# MCU.net
KiCad netlist of a schematic drawn in Altium Designer
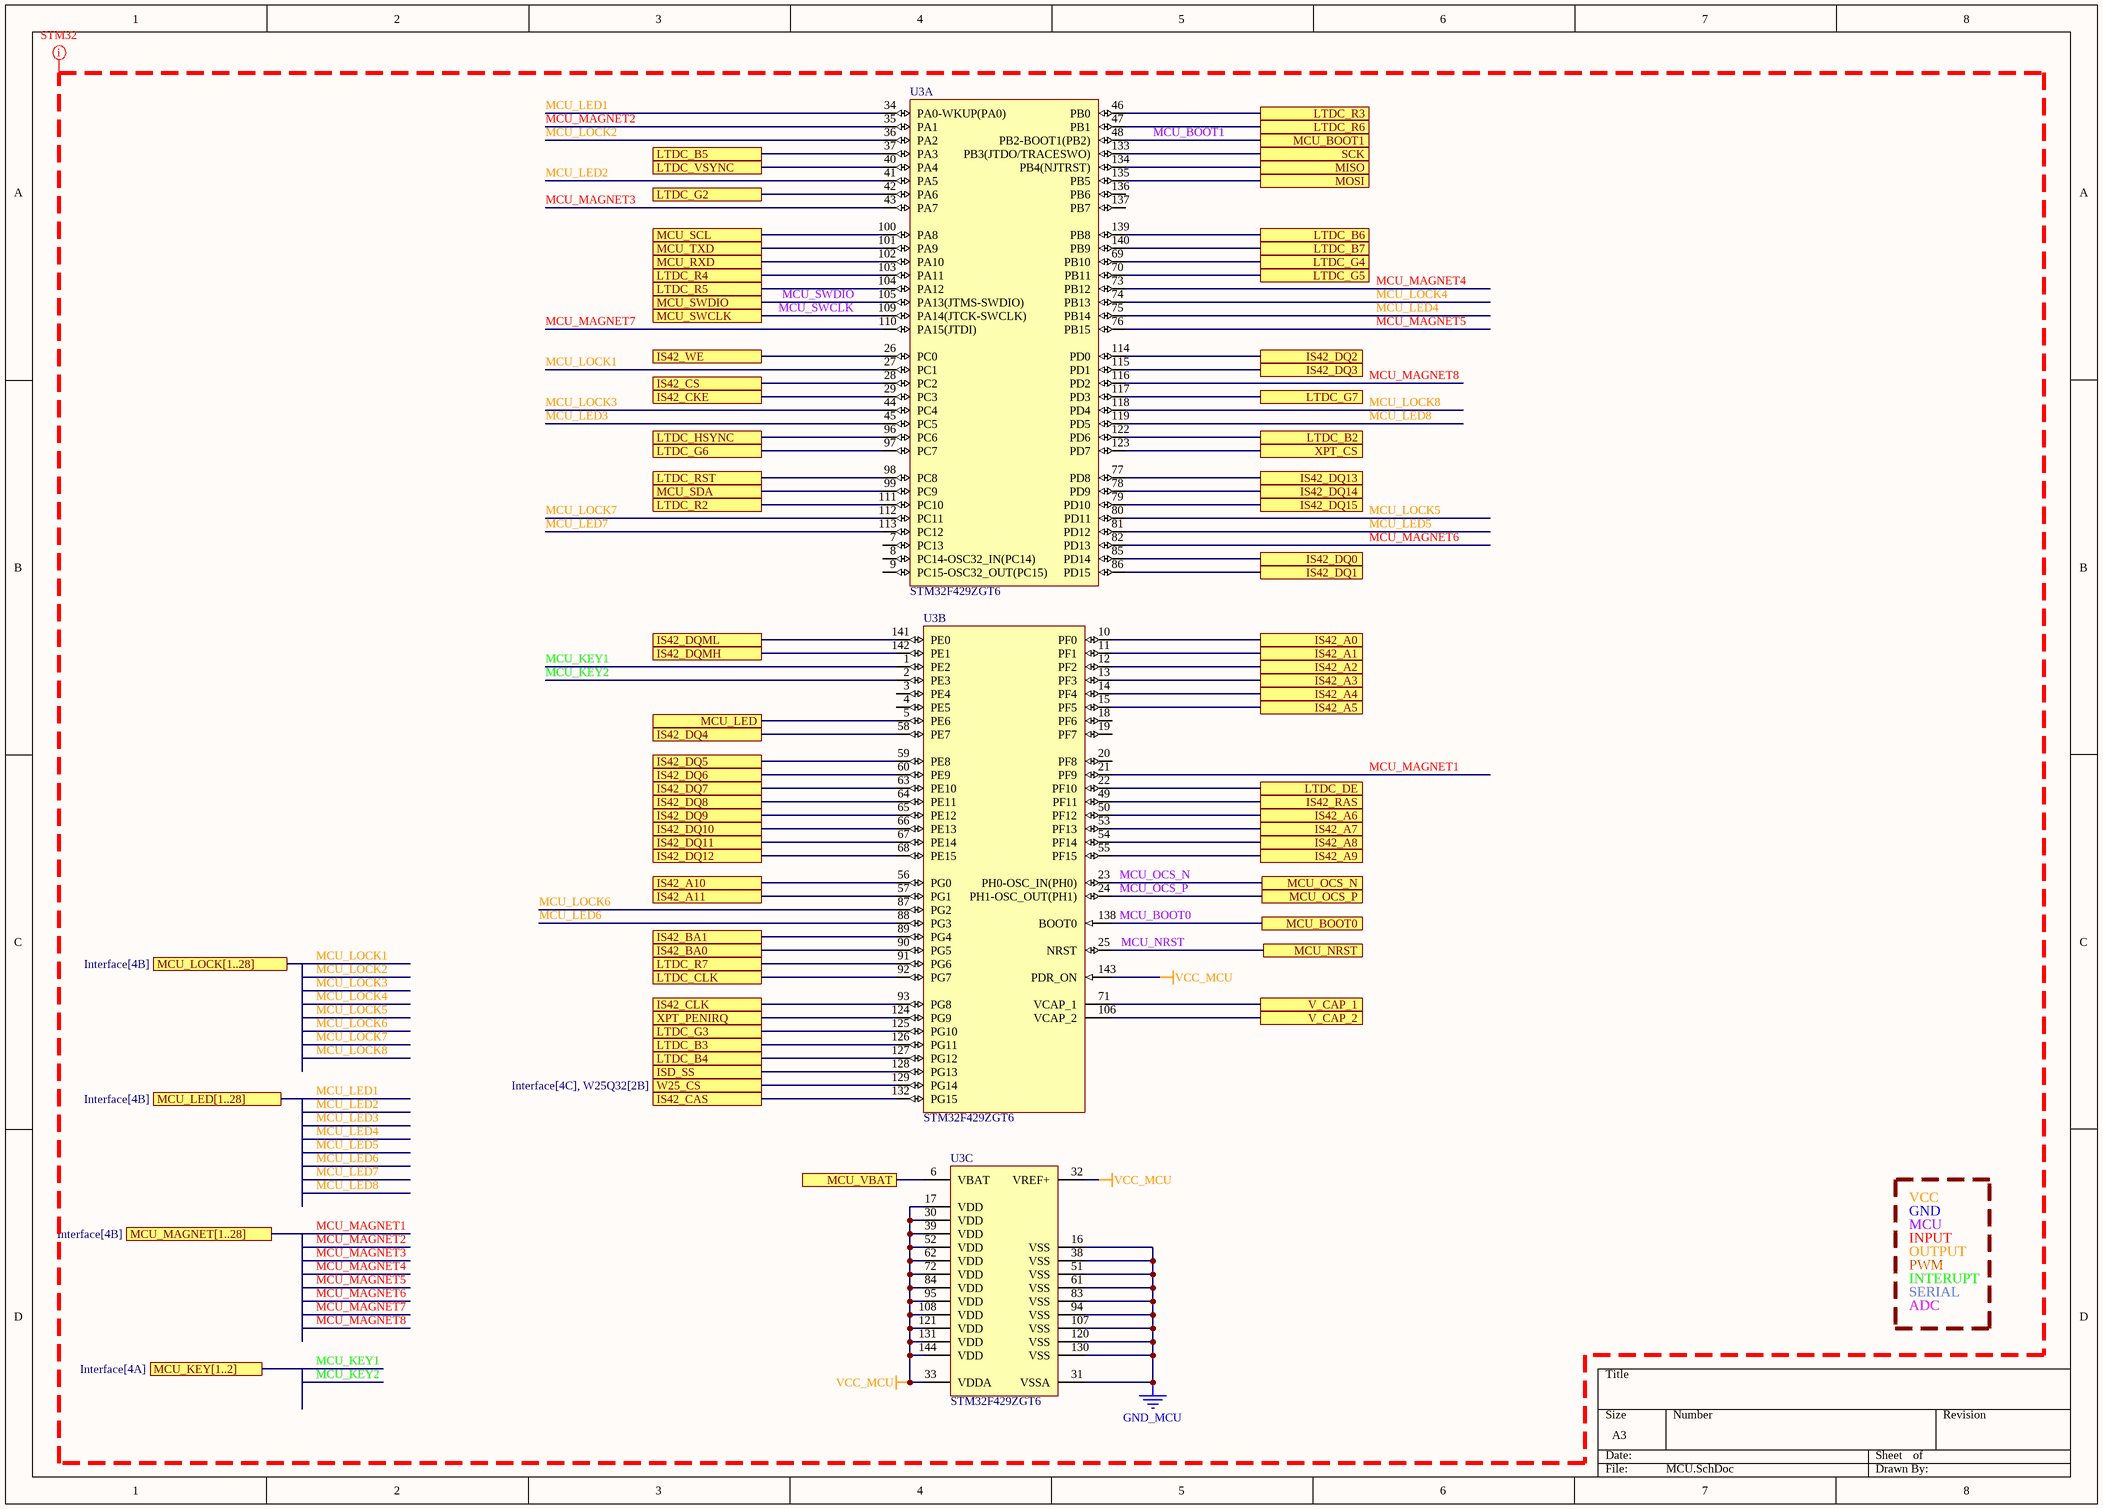
[diagram p0: MCU.SchDoc]

(export (version "E")
  (design (tool "Eeschema 10.0.6"))
  (components
    (comp (ref "U3")
      (value "STM32F429ZGT6")
      (footprint "STM-LQFP144_N")
      (fields (field (name "MANUFACTURER") "STMicroelectronics"))
      (libsource (lib "ST Microelectronics STM32 F4") (part "STM32F429ZGT6"))
    )
  )
  (nets
    (net (code "61") (name "/IS42_A0") (class "Default")
      (node (ref "U3") (pin "10") (pinfunction "PF0_10") (pintype "bidirectional"))
    )
    (net (code "62") (name "/IS42_A1") (class "Default")
      (node (ref "U3") (pin "11") (pinfunction "PF1_11") (pintype "bidirectional"))
    )
    (net (code "63") (name "/IS42_A2") (class "Default")
      (node (ref "U3") (pin "12") (pinfunction "PF2_12") (pintype "bidirectional"))
    )
    (net (code "64") (name "/IS42_A3") (class "Default")
      (node (ref "U3") (pin "13") (pinfunction "PF3_13") (pintype "bidirectional"))
    )
    (net (code "65") (name "/IS42_A4") (class "Default")
      (node (ref "U3") (pin "14") (pinfunction "PF4_14") (pintype "bidirectional"))
    )
    (net (code "66") (name "/IS42_A5") (class "Default")
      (node (ref "U3") (pin "15") (pinfunction "PF5_15") (pintype "bidirectional"))
    )
    (net (code "67") (name "/IS42_A6") (class "Default")
      (node (ref "U3") (pin "50") (pinfunction "PF12_50") (pintype "bidirectional"))
    )
    (net (code "68") (name "/IS42_A7") (class "Default")
      (node (ref "U3") (pin "53") (pinfunction "PF13_53") (pintype "bidirectional"))
    )
    (net (code "69") (name "/IS42_A8") (class "Default")
      (node (ref "U3") (pin "54") (pinfunction "PF14_54") (pintype "bidirectional"))
    )
    (net (code "70") (name "/IS42_A9") (class "Default")
      (node (ref "U3") (pin "55") (pinfunction "PF15_55") (pintype "bidirectional"))
    )
    (net (code "71") (name "/IS42_A10") (class "Default")
      (node (ref "U3") (pin "56") (pinfunction "PG0_56") (pintype "bidirectional"))
    )
    (net (code "72") (name "/IS42_A11") (class "Default")
      (node (ref "U3") (pin "57") (pinfunction "PG1_57") (pintype "bidirectional"))
    )
    (net (code "73") (name "/IS42_BA0") (class "Default")
      (node (ref "U3") (pin "90") (pinfunction "PG5_90") (pintype "bidirectional"))
    )
    (net (code "74") (name "/IS42_BA1") (class "Default")
      (node (ref "U3") (pin "89") (pinfunction "PG4_89") (pintype "bidirectional"))
    )
    (net (code "75") (name "/IS42_CAS") (class "Default")
      (node (ref "U3") (pin "132") (pinfunction "PG15_132") (pintype "bidirectional"))
    )
    (net (code "76") (name "/IS42_CKE") (class "Default")
      (node (ref "U3") (pin "29") (pinfunction "PC3_29") (pintype "bidirectional"))
    )
    (net (code "77") (name "/IS42_CLK") (class "Default")
      (node (ref "U3") (pin "93") (pinfunction "PG8_93") (pintype "bidirectional"))
    )
    (net (code "78") (name "/IS42_CS") (class "Default")
      (node (ref "U3") (pin "28") (pinfunction "PC2_28") (pintype "bidirectional"))
    )
    (net (code "79") (name "/IS42_DQ0") (class "Default")
      (node (ref "U3") (pin "85") (pinfunction "PD14_85") (pintype "bidirectional"))
    )
    (net (code "80") (name "/IS42_DQ1") (class "Default")
      (node (ref "U3") (pin "86") (pinfunction "PD15_86") (pintype "bidirectional"))
    )
    (net (code "81") (name "/IS42_DQ2") (class "Default")
      (node (ref "U3") (pin "114") (pinfunction "PD0_114") (pintype "bidirectional"))
    )
    (net (code "82") (name "/IS42_DQ3") (class "Default")
      (node (ref "U3") (pin "115") (pinfunction "PD1_115") (pintype "bidirectional"))
    )
    (net (code "83") (name "/IS42_DQ4") (class "Default")
      (node (ref "U3") (pin "58") (pinfunction "PE7_58") (pintype "bidirectional"))
    )
    (net (code "84") (name "/IS42_DQ5") (class "Default")
      (node (ref "U3") (pin "59") (pinfunction "PE8_59") (pintype "bidirectional"))
    )
    (net (code "85") (name "/IS42_DQ6") (class "Default")
      (node (ref "U3") (pin "60") (pinfunction "PE9_60") (pintype "bidirectional"))
    )
    (net (code "86") (name "/IS42_DQ7") (class "Default")
      (node (ref "U3") (pin "63") (pinfunction "PE10_63") (pintype "bidirectional"))
    )
    (net (code "87") (name "/IS42_DQ8") (class "Default")
      (node (ref "U3") (pin "64") (pinfunction "PE11_64") (pintype "bidirectional"))
    )
    (net (code "88") (name "/IS42_DQ9") (class "Default")
      (node (ref "U3") (pin "65") (pinfunction "PE12_65") (pintype "bidirectional"))
    )
    (net (code "89") (name "/IS42_DQ10") (class "Default")
      (node (ref "U3") (pin "66") (pinfunction "PE13_66") (pintype "bidirectional"))
    )
    (net (code "90") (name "/IS42_DQ11") (class "Default")
      (node (ref "U3") (pin "67") (pinfunction "PE14_67") (pintype "bidirectional"))
    )
    (net (code "91") (name "/IS42_DQ12") (class "Default")
      (node (ref "U3") (pin "68") (pinfunction "PE15_68") (pintype "bidirectional"))
    )
    (net (code "92") (name "/IS42_DQ13") (class "Default")
      (node (ref "U3") (pin "77") (pinfunction "PD8_77") (pintype "bidirectional"))
    )
    (net (code "93") (name "/IS42_DQ14") (class "Default")
      (node (ref "U3") (pin "78") (pinfunction "PD9_78") (pintype "bidirectional"))
    )
    (net (code "94") (name "/IS42_DQ15") (class "Default")
      (node (ref "U3") (pin "79") (pinfunction "PD10_79") (pintype "bidirectional"))
    )
    (net (code "95") (name "/IS42_DQMH") (class "Default")
      (node (ref "U3") (pin "142") (pinfunction "PE1_142") (pintype "bidirectional"))
    )
    (net (code "96") (name "/IS42_DQML") (class "Default")
      (node (ref "U3") (pin "141") (pinfunction "PE0_141") (pintype "bidirectional"))
    )
    (net (code "97") (name "/IS42_RAS") (class "Default")
      (node (ref "U3") (pin "49") (pinfunction "PF11_49") (pintype "bidirectional"))
    )
    (net (code "98") (name "/IS42_WE") (class "Default")
      (node (ref "U3") (pin "26") (pinfunction "PC0_26") (pintype "bidirectional"))
    )
    (net (code "99") (name "/ISD_SS") (class "Default")
      (node (ref "U3") (pin "128") (pinfunction "PG13_128") (pintype "bidirectional"))
    )
    (net (code "100") (name "/LTDC_B2") (class "Default")
      (node (ref "U3") (pin "122") (pinfunction "PD6_122") (pintype "bidirectional"))
    )
    (net (code "101") (name "/LTDC_B3") (class "Default")
      (node (ref "U3") (pin "126") (pinfunction "PG11_126") (pintype "bidirectional"))
    )
    (net (code "102") (name "/LTDC_B4") (class "Default")
      (node (ref "U3") (pin "127") (pinfunction "PG12_127") (pintype "bidirectional"))
    )
    (net (code "103") (name "/LTDC_B5") (class "Default")
      (node (ref "U3") (pin "37") (pinfunction "PA3_37") (pintype "bidirectional"))
    )
    (net (code "104") (name "/LTDC_B6") (class "Default")
      (node (ref "U3") (pin "139") (pinfunction "PB8_139") (pintype "bidirectional"))
    )
    (net (code "105") (name "/LTDC_B7") (class "Default")
      (node (ref "U3") (pin "140") (pinfunction "PB9_140") (pintype "bidirectional"))
    )
    (net (code "106") (name "/LTDC_CLK") (class "Default")
      (node (ref "U3") (pin "92") (pinfunction "PG7_92") (pintype "bidirectional"))
    )
    (net (code "107") (name "/LTDC_DE") (class "Default")
      (node (ref "U3") (pin "22") (pinfunction "PF10_22") (pintype "bidirectional"))
    )
    (net (code "108") (name "/LTDC_G2") (class "Default")
      (node (ref "U3") (pin "42") (pinfunction "PA6_42") (pintype "bidirectional"))
    )
    (net (code "109") (name "/LTDC_G3") (class "Default")
      (node (ref "U3") (pin "125") (pinfunction "PG10_125") (pintype "bidirectional"))
    )
    (net (code "110") (name "/LTDC_G4") (class "Default")
      (node (ref "U3") (pin "69") (pinfunction "PB10_69") (pintype "bidirectional"))
    )
    (net (code "111") (name "/LTDC_G5") (class "Default")
      (node (ref "U3") (pin "70") (pinfunction "PB11_70") (pintype "bidirectional"))
    )
    (net (code "112") (name "/LTDC_G6") (class "Default")
      (node (ref "U3") (pin "97") (pinfunction "PC7_97") (pintype "bidirectional"))
    )
    (net (code "113") (name "/LTDC_G7") (class "Default")
      (node (ref "U3") (pin "117") (pinfunction "PD3_117") (pintype "bidirectional"))
    )
    (net (code "114") (name "/LTDC_HSYNC") (class "Default")
      (node (ref "U3") (pin "96") (pinfunction "PC6_96") (pintype "bidirectional"))
    )
    (net (code "115") (name "/LTDC_R2") (class "Default")
      (node (ref "U3") (pin "111") (pinfunction "PC10_111") (pintype "bidirectional"))
    )
    (net (code "116") (name "/LTDC_R3") (class "Default")
      (node (ref "U3") (pin "46") (pinfunction "PB0_46") (pintype "bidirectional"))
    )
    (net (code "117") (name "/LTDC_R4") (class "Default")
      (node (ref "U3") (pin "103") (pinfunction "PA11_103") (pintype "bidirectional"))
    )
    (net (code "118") (name "/LTDC_R5") (class "Default")
      (node (ref "U3") (pin "104") (pinfunction "PA12_104") (pintype "bidirectional"))
    )
    (net (code "119") (name "/LTDC_R6") (class "Default")
      (node (ref "U3") (pin "47") (pinfunction "PB1_47") (pintype "bidirectional"))
    )
    (net (code "120") (name "/LTDC_R7") (class "Default")
      (node (ref "U3") (pin "91") (pinfunction "PG6_91") (pintype "bidirectional"))
    )
    (net (code "121") (name "/LTDC_RST") (class "Default")
      (node (ref "U3") (pin "98") (pinfunction "PC8_98") (pintype "bidirectional"))
    )
    (net (code "122") (name "/LTDC_VSYNC") (class "Default")
      (node (ref "U3") (pin "40") (pinfunction "PA4_40") (pintype "bidirectional"))
    )
    (net (code "123") (name "/MCU_BOOT0") (class "Default")
      (node (ref "U3") (pin "138") (pinfunction "BOOT0_138") (pintype "input"))
    )
    (net (code "124") (name "/MCU_BOOT1") (class "Default")
      (node (ref "U3") (pin "48") (pinfunction "PB2-BOOT1(PB2)_48") (pintype "bidirectional"))
    )
    (net (code "125") (name "/MCU_KEY1") (class "Default")
      (node (ref "U3") (pin "1") (pinfunction "PE2_1") (pintype "bidirectional"))
    )
    (net (code "126") (name "/MCU_KEY2") (class "Default")
      (node (ref "U3") (pin "2") (pinfunction "PE3_2") (pintype "bidirectional"))
    )
    (net (code "128") (name "/MCU_LED") (class "Default")
      (node (ref "U3") (pin "5") (pinfunction "PE6_5") (pintype "bidirectional"))
    )
    (net (code "129") (name "/MCU_LED1") (class "Default")
      (node (ref "U3") (pin "34") (pinfunction "PA0-WKUP(PA0)_34") (pintype "bidirectional"))
    )
    (net (code "130") (name "/MCU_LED2") (class "Default")
      (node (ref "U3") (pin "41") (pinfunction "PA5_41") (pintype "bidirectional"))
    )
    (net (code "131") (name "/MCU_LED3") (class "Default")
      (node (ref "U3") (pin "45") (pinfunction "PC5_45") (pintype "bidirectional"))
    )
    (net (code "132") (name "/MCU_LED4") (class "Default")
      (node (ref "U3") (pin "75") (pinfunction "PB14_75") (pintype "bidirectional"))
    )
    (net (code "133") (name "/MCU_LED5") (class "Default")
      (node (ref "U3") (pin "81") (pinfunction "PD12_81") (pintype "bidirectional"))
    )
    (net (code "134") (name "/MCU_LED6") (class "Default")
      (node (ref "U3") (pin "88") (pinfunction "PG3_88") (pintype "bidirectional"))
    )
    (net (code "135") (name "/MCU_LED7") (class "Default")
      (node (ref "U3") (pin "113") (pinfunction "PC12_113") (pintype "bidirectional"))
    )
    (net (code "136") (name "/MCU_LED8") (class "Default")
      (node (ref "U3") (pin "119") (pinfunction "PD5_119") (pintype "bidirectional"))
    )
    (net (code "138") (name "/MCU_LOCK1") (class "Default")
      (node (ref "U3") (pin "27") (pinfunction "PC1_27") (pintype "bidirectional"))
    )
    (net (code "139") (name "/MCU_LOCK2") (class "Default")
      (node (ref "U3") (pin "36") (pinfunction "PA2_36") (pintype "bidirectional"))
    )
    (net (code "140") (name "/MCU_LOCK3") (class "Default")
      (node (ref "U3") (pin "44") (pinfunction "PC4_44") (pintype "bidirectional"))
    )
    (net (code "141") (name "/MCU_LOCK4") (class "Default")
      (node (ref "U3") (pin "74") (pinfunction "PB13_74") (pintype "bidirectional"))
    )
    (net (code "142") (name "/MCU_LOCK5") (class "Default")
      (node (ref "U3") (pin "80") (pinfunction "PD11_80") (pintype "bidirectional"))
    )
    (net (code "143") (name "/MCU_LOCK6") (class "Default")
      (node (ref "U3") (pin "87") (pinfunction "PG2_87") (pintype "bidirectional"))
    )
    (net (code "144") (name "/MCU_LOCK7") (class "Default")
      (node (ref "U3") (pin "112") (pinfunction "PC11_112") (pintype "bidirectional"))
    )
    (net (code "145") (name "/MCU_LOCK8") (class "Default")
      (node (ref "U3") (pin "118") (pinfunction "PD4_118") (pintype "bidirectional"))
    )
    (net (code "147") (name "/MCU_MAGNET1") (class "Default")
      (node (ref "U3") (pin "21") (pinfunction "PF9_21") (pintype "bidirectional"))
    )
    (net (code "148") (name "/MCU_MAGNET2") (class "Default")
      (node (ref "U3") (pin "35") (pinfunction "PA1_35") (pintype "bidirectional"))
    )
    (net (code "149") (name "/MCU_MAGNET3") (class "Default")
      (node (ref "U3") (pin "43") (pinfunction "PA7_43") (pintype "bidirectional"))
    )
    (net (code "150") (name "/MCU_MAGNET4") (class "Default")
      (node (ref "U3") (pin "73") (pinfunction "PB12_73") (pintype "bidirectional"))
    )
    (net (code "151") (name "/MCU_MAGNET5") (class "Default")
      (node (ref "U3") (pin "76") (pinfunction "PB15_76") (pintype "bidirectional"))
    )
    (net (code "152") (name "/MCU_MAGNET6") (class "Default")
      (node (ref "U3") (pin "82") (pinfunction "PD13_82") (pintype "bidirectional"))
    )
    (net (code "153") (name "/MCU_MAGNET7") (class "Default")
      (node (ref "U3") (pin "110") (pinfunction "PA15(JTDI)_110") (pintype "bidirectional"))
    )
    (net (code "154") (name "/MCU_MAGNET8") (class "Default")
      (node (ref "U3") (pin "116") (pinfunction "PD2_116") (pintype "bidirectional"))
    )
    (net (code "156") (name "/MCU_NRST") (class "Default")
      (node (ref "U3") (pin "25") (pinfunction "NRST_25") (pintype "bidirectional"))
    )
    (net (code "157") (name "/MCU_OCS_N") (class "Default")
      (node (ref "U3") (pin "23") (pinfunction "PH0-OSC_IN(PH0)_23") (pintype "bidirectional"))
    )
    (net (code "158") (name "/MCU_OCS_P") (class "Default")
      (node (ref "U3") (pin "24") (pinfunction "PH1-OSC_OUT(PH1)_24") (pintype "bidirectional"))
    )
    (net (code "159") (name "/MCU_RXD") (class "Default")
      (node (ref "U3") (pin "102") (pinfunction "PA10_102") (pintype "bidirectional"))
    )
    (net (code "160") (name "/MCU_SCL") (class "Default")
      (node (ref "U3") (pin "100") (pinfunction "PA8_100") (pintype "bidirectional"))
    )
    (net (code "161") (name "/MCU_SDA") (class "Default")
      (node (ref "U3") (pin "99") (pinfunction "PC9_99") (pintype "bidirectional"))
    )
    (net (code "162") (name "/MCU_SWCLK") (class "Default")
      (node (ref "U3") (pin "109") (pinfunction "PA14(JTCK-SWCLK)_109") (pintype "bidirectional"))
    )
    (net (code "163") (name "/MCU_SWDIO") (class "Default")
      (node (ref "U3") (pin "105") (pinfunction "PA13(JTMS-SWDIO)_105") (pintype "bidirectional"))
    )
    (net (code "164") (name "/MCU_TXD") (class "Default")
      (node (ref "U3") (pin "101") (pinfunction "PA9_101") (pintype "bidirectional"))
    )
    (net (code "165") (name "/MCU_VBAT") (class "Default")
      (node (ref "U3") (pin "6") (pinfunction "VBAT_6") (pintype "power_in"))
    )
    (net (code "166") (name "/MISO") (class "Default")
      (node (ref "U3") (pin "134") (pinfunction "PB4(NJTRST)_134") (pintype "bidirectional"))
    )
    (net (code "167") (name "/MOSI") (class "Default")
      (node (ref "U3") (pin "135") (pinfunction "PB5_135") (pintype "bidirectional"))
    )
    (net (code "168") (name "/SCK") (class "Default")
      (node (ref "U3") (pin "133") (pinfunction "PB3(JTDO/TRACESWO)_133") (pintype "bidirectional"))
    )
    (net (code "169") (name "/V_CAP_1") (class "Default")
      (node (ref "U3") (pin "71") (pinfunction "VCAP_1_71") (pintype "power_in"))
    )
    (net (code "170") (name "/V_CAP_2") (class "Default")
      (node (ref "U3") (pin "106") (pinfunction "VCAP_2_106") (pintype "power_in"))
    )
    (net (code "171") (name "/W25_CS") (class "Default")
      (node (ref "U3") (pin "129") (pinfunction "PG14_129") (pintype "bidirectional"))
    )
    (net (code "172") (name "/XPT_CS") (class "Default")
      (node (ref "U3") (pin "123") (pinfunction "PD7_123") (pintype "bidirectional"))
    )
    (net (code "173") (name "/XPT_PENIRQ") (class "Default")
      (node (ref "U3") (pin "124") (pinfunction "PG9_124") (pintype "bidirectional"))
    )
    (net (code "174") (name "GND_MCU") (class "Default")
      (node (ref "U3") (pin "107") (pinfunction "VSS_107") (pintype "power_in"))
      (node (ref "U3") (pin "120") (pinfunction "VSS_120") (pintype "power_in"))
      (node (ref "U3") (pin "130") (pinfunction "VSS_130") (pintype "power_in"))
      (node (ref "U3") (pin "16") (pinfunction "VSS_16") (pintype "power_in"))
      (node (ref "U3") (pin "31") (pinfunction "VSSA_31") (pintype "power_in"))
      (node (ref "U3") (pin "38") (pinfunction "VSS_38") (pintype "power_in"))
      (node (ref "U3") (pin "51") (pinfunction "VSS_51") (pintype "power_in"))
      (node (ref "U3") (pin "61") (pinfunction "VSS_61") (pintype "power_in"))
      (node (ref "U3") (pin "83") (pinfunction "VSS_83") (pintype "power_in"))
      (node (ref "U3") (pin "94") (pinfunction "VSS_94") (pintype "power_in"))
    )
    (net (code "175") (name "VCC_MCU") (class "Default")
      (node (ref "U3") (pin "108") (pinfunction "VDD_108") (pintype "power_in"))
      (node (ref "U3") (pin "121") (pinfunction "VDD_121") (pintype "power_in"))
      (node (ref "U3") (pin "131") (pinfunction "VDD_131") (pintype "power_in"))
      (node (ref "U3") (pin "143") (pinfunction "PDR_ON_143") (pintype "input"))
      (node (ref "U3") (pin "144") (pinfunction "VDD_144") (pintype "power_in"))
      (node (ref "U3") (pin "17") (pinfunction "VDD_17") (pintype "power_in"))
      (node (ref "U3") (pin "30") (pinfunction "VDD_30") (pintype "power_in"))
      (node (ref "U3") (pin "32") (pinfunction "VREF+_32") (pintype "power_in"))
      (node (ref "U3") (pin "33") (pinfunction "VDDA_33") (pintype "power_in"))
      (node (ref "U3") (pin "39") (pinfunction "VDD_39") (pintype "power_in"))
      (node (ref "U3") (pin "52") (pinfunction "VDD_52") (pintype "power_in"))
      (node (ref "U3") (pin "62") (pinfunction "VDD_62") (pintype "power_in"))
      (node (ref "U3") (pin "72") (pinfunction "VDD_72") (pintype "power_in"))
      (node (ref "U3") (pin "84") (pinfunction "VDD_84") (pintype "power_in"))
      (node (ref "U3") (pin "95") (pinfunction "VDD_95") (pintype "power_in"))
    )
    (net (code "176") (name "unconnected-(U3A-PB6-Pad136)") (class "Default")
      (node (ref "U3") (pin "136") (pinfunction "PB6_136") (pintype "bidirectional"))
    )
    (net (code "177") (name "unconnected-(U3A-PB7-Pad137)") (class "Default")
      (node (ref "U3") (pin "137") (pinfunction "PB7_137") (pintype "bidirectional"))
    )
    (net (code "178") (name "unconnected-(U3A-PC13-Pad7)") (class "Default")
      (node (ref "U3") (pin "7") (pinfunction "PC13_7") (pintype "bidirectional"))
    )
    (net (code "179") (name "unconnected-(U3A-PC14-OSC32_IN(PC14)-Pad8)") (class "Default")
      (node (ref "U3") (pin "8") (pinfunction "PC14-OSC32_IN(PC14)_8") (pintype "bidirectional"))
    )
    (net (code "180") (name "unconnected-(U3A-PC15-OSC32_OUT(PC15)-Pad9)") (class "Default")
      (node (ref "U3") (pin "9") (pinfunction "PC15-OSC32_OUT(PC15)_9") (pintype "bidirectional"))
    )
    (net (code "181") (name "unconnected-(U3B-PE4-Pad3)") (class "Default")
      (node (ref "U3") (pin "3") (pinfunction "PE4_3") (pintype "bidirectional"))
    )
    (net (code "182") (name "unconnected-(U3B-PE5-Pad4)") (class "Default")
      (node (ref "U3") (pin "4") (pinfunction "PE5_4") (pintype "bidirectional"))
    )
    (net (code "183") (name "unconnected-(U3B-PF6-Pad18)") (class "Default")
      (node (ref "U3") (pin "18") (pinfunction "PF6_18") (pintype "bidirectional"))
    )
    (net (code "184") (name "unconnected-(U3B-PF7-Pad19)") (class "Default")
      (node (ref "U3") (pin "19") (pinfunction "PF7_19") (pintype "bidirectional"))
    )
    (net (code "185") (name "unconnected-(U3B-PF8-Pad20)") (class "Default")
      (node (ref "U3") (pin "20") (pinfunction "PF8_20") (pintype "bidirectional"))
    )
  )
)
